# ctrlr_w_MCP4912.net
KiCad netlist of a schematic drawn in EAGLE
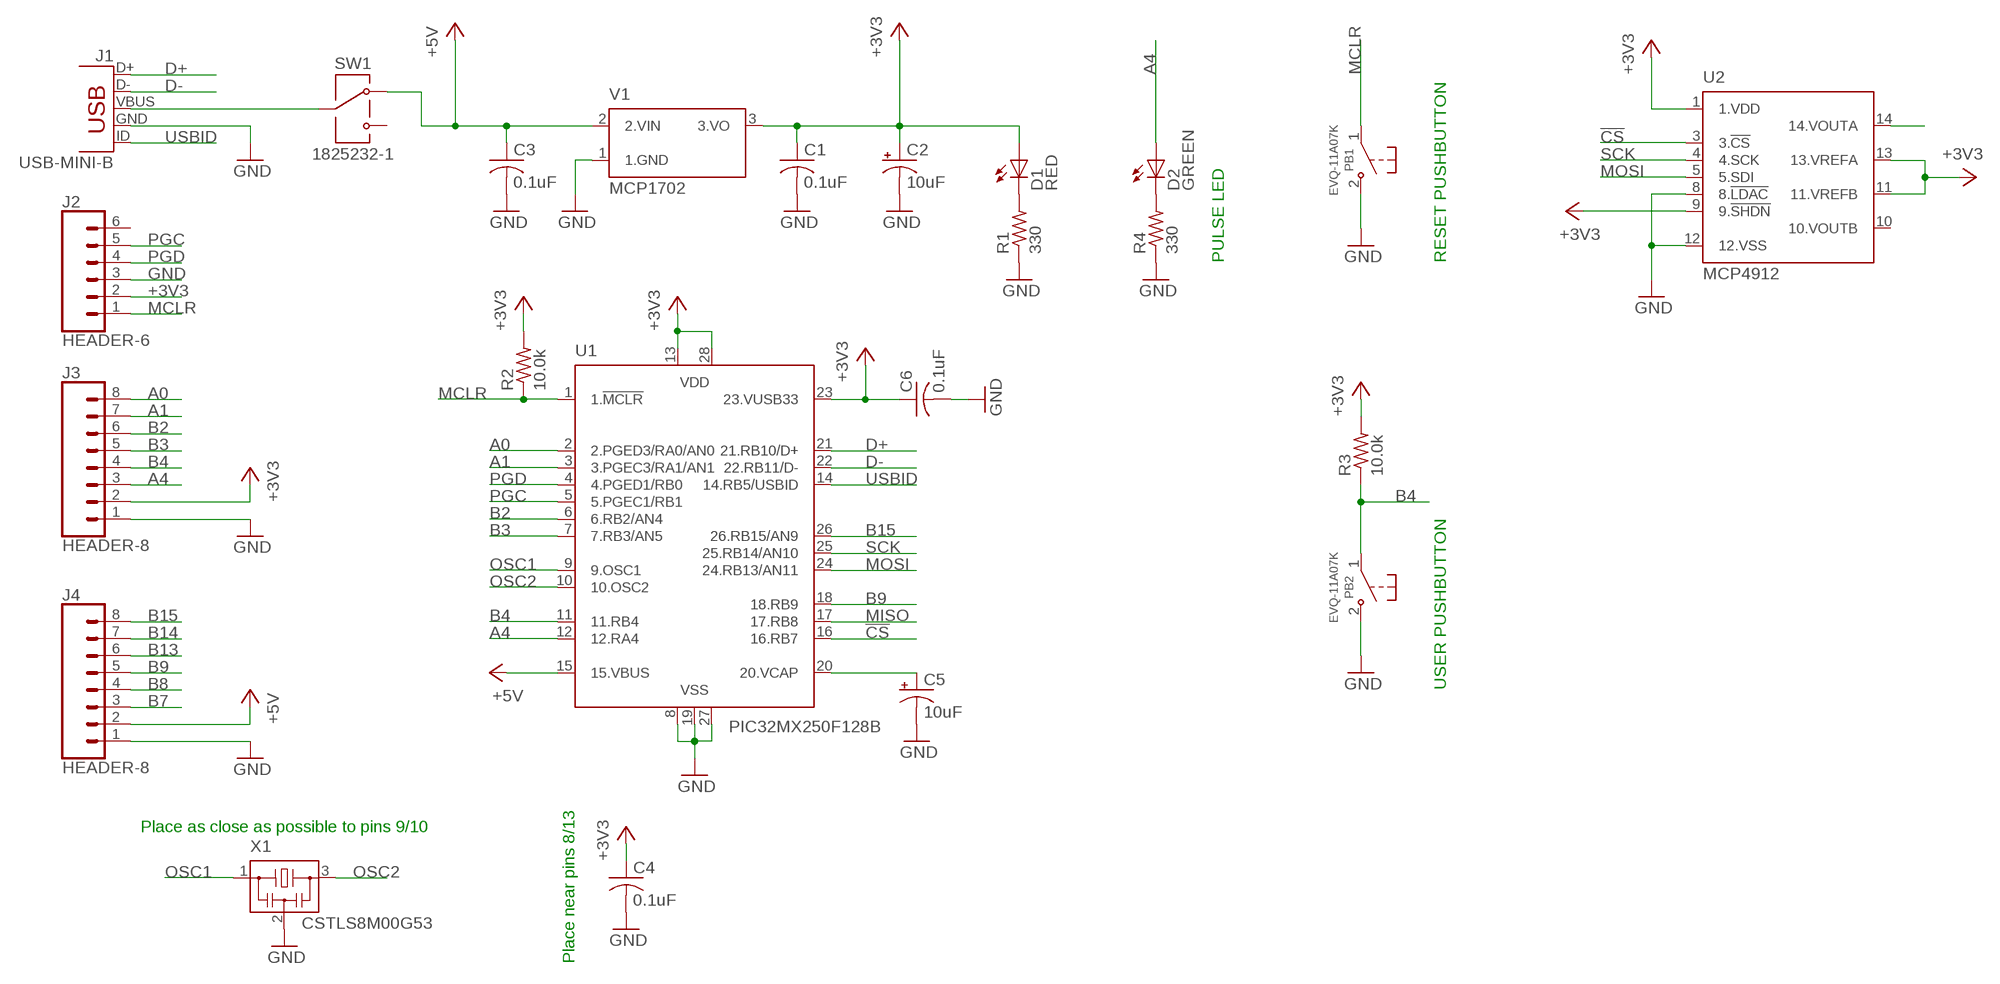
[diagram p0: schematic, sheet 1]

(export (version "E")
  (design (tool "Eeschema 10.0.6"))
  (components
    (comp (ref "C1")
      (value "0.1uF")
      (footprint "eagle-import:C1206")
      (libsource (lib "eagle-import") (part "C-USC1206"))
    )
    (comp (ref "C2")
      (value "10uF")
      (footprint "eagle-import:TAP5-50")
      (libsource (lib "eagle-import") (part "CPOL-USTAP5-50"))
    )
    (comp (ref "C3")
      (value "0.1uF")
      (footprint "eagle-import:C1206")
      (libsource (lib "eagle-import") (part "C-USC1206"))
    )
    (comp (ref "C4")
      (value "0.1uF")
      (footprint "eagle-import:C1206")
      (libsource (lib "eagle-import") (part "C-USC1206"))
    )
    (comp (ref "C5")
      (value "10uF")
      (footprint "eagle-import:TAP5-50")
      (libsource (lib "eagle-import") (part "CPOL-USTAP5-50"))
    )
    (comp (ref "C6")
      (value "0.1uF")
      (footprint "eagle-import:C1206")
      (libsource (lib "eagle-import") (part "C-USC1206"))
    )
    (comp (ref "D1")
      (value "LED-RED")
      (footprint "eagle-import:LED-3MM-V")
      (libsource (lib "eagle-import") (part "LED-RED"))
    )
    (comp (ref "D2")
      (value "LED-GREEN")
      (footprint "eagle-import:LED-3MM-V")
      (libsource (lib "eagle-import") (part "LED-GREEN"))
    )
    (comp (ref "J1")
      (value "USB-MINI-B")
      (footprint "eagle-import:USB-MB-TO")
      (libsource (lib "eagle-import") (part "USB-MINI-B"))
    )
    (comp (ref "J2")
      (value "HEADER-6")
      (footprint "eagle-import:CONN_1X06")
      (libsource (lib "eagle-import") (part "HEADER-6"))
    )
    (comp (ref "J3")
      (value "HEADER-8")
      (footprint "eagle-import:CONN_1X08")
      (libsource (lib "eagle-import") (part "HEADER-8"))
    )
    (comp (ref "J4")
      (value "HEADER-8")
      (footprint "eagle-import:CONN_1X08")
      (libsource (lib "eagle-import") (part "HEADER-8"))
    )
    (comp (ref "PB1")
      (value "EVQ-11A07K")
      (footprint "eagle-import:PCPIN-2")
      (libsource (lib "eagle-import") (part "EVQ-11A07K"))
    )
    (comp (ref "PB2")
      (value "EVQ-11A07K")
      (footprint "eagle-import:PCPIN-2")
      (libsource (lib "eagle-import") (part "EVQ-11A07K"))
    )
    (comp (ref "R1")
      (value "330")
      (footprint "eagle-import:R1206")
      (libsource (lib "eagle-import") (part "R-US_R1206"))
    )
    (comp (ref "R2")
      (value "10.0k")
      (footprint "eagle-import:R1206")
      (libsource (lib "eagle-import") (part "R-US_R1206"))
    )
    (comp (ref "R3")
      (value "10.0k")
      (footprint "eagle-import:R1206")
      (libsource (lib "eagle-import") (part "R-US_R1206"))
    )
    (comp (ref "R4")
      (value "330")
      (footprint "eagle-import:R1206")
      (libsource (lib "eagle-import") (part "R-US_R1206"))
    )
    (comp (ref "SW1")
      (value "1825232-1")
      (footprint "eagle-import:PCPIN-3SS")
      (libsource (lib "eagle-import") (part "1825232-1"))
    )
    (comp (ref "U1")
      (value "PIC32MX250F128B")
      (footprint "eagle-import:DIP28-3")
      (libsource (lib "eagle-import") (part "PIC32MX250F128B"))
    )
    (comp (ref "U2")
      (value "MCP4912")
      (footprint "eagle-import:DIP14-3")
      (libsource (lib "eagle-import") (part "MCP4912"))
    )
    (comp (ref "V1")
      (value "MCP1702")
      (footprint "eagle-import:TO-92")
      (libsource (lib "eagle-import") (part "MCP1702"))
    )
    (comp (ref "X1")
      (value "CSTLS8M00G53")
      (footprint "eagle-import:RAD-3-2.5")
      (libsource (lib "eagle-import") (part "CSTLS8M00G53"))
    )
  )
  (nets
    (net (code "1") (name "+3V3") (class "Default")
      (node (ref "C1") (pin "1") (pinfunction "1_1") (pintype "passive"))
      (node (ref "C2") (pin "+") (pinfunction "+_+") (pintype "passive"))
      (node (ref "C4") (pin "1") (pinfunction "1_1") (pintype "passive"))
      (node (ref "C6") (pin "1") (pinfunction "1_1") (pintype "passive"))
      (node (ref "D1") (pin "A") (pinfunction "A_A") (pintype "passive"))
      (node (ref "J2") (pin "2") (pinfunction "2._2") (pintype "passive"))
      (node (ref "J3") (pin "2") (pinfunction "2._2") (pintype "passive"))
      (node (ref "R2") (pin "2") (pinfunction "2_2") (pintype "passive"))
      (node (ref "R3") (pin "2") (pinfunction "2_2") (pintype "passive"))
      (node (ref "U1") (pin "13") (pinfunction "13.VDD_13") (pintype "power_in"))
      (node (ref "U1") (pin "23") (pinfunction "23.VUSB33_23") (pintype "bidirectional"))
      (node (ref "U1") (pin "28") (pinfunction "28.AVDD_28") (pintype "power_in"))
      (node (ref "U2") (pin "1") (pinfunction "1.VDD_1") (pintype "input"))
      (node (ref "U2") (pin "11") (pinfunction "11.VREFB_11") (pintype "input"))
      (node (ref "U2") (pin "13") (pinfunction "13.VREFA_13") (pintype "input"))
      (node (ref "U2") (pin "9") (pinfunction "9.~{SHDN}_9") (pintype "input"))
      (node (ref "V1") (pin "3") (pinfunction "3.VO_3") (pintype "output"))
    )
    (net (code "2") (name "+5V") (class "Default")
      (node (ref "C3") (pin "1") (pinfunction "1_1") (pintype "passive"))
      (node (ref "J4") (pin "2") (pinfunction "2._2") (pintype "passive"))
      (node (ref "SW1") (pin "1") (pinfunction "1_1") (pintype "bidirectional"))
      (node (ref "U1") (pin "15") (pinfunction "15.VBUS_15") (pintype "bidirectional"))
      (node (ref "V1") (pin "2") (pinfunction "2.VIN_2") (pintype "input"))
    )
    (net (code "3") (name "/A0") (class "Default")
      (node (ref "J3") (pin "8") (pinfunction "8._8") (pintype "passive"))
      (node (ref "U1") (pin "2") (pinfunction "2.PGED3/RA0/AN0_2") (pintype "bidirectional"))
    )
    (net (code "4") (name "/A1") (class "Default")
      (node (ref "J3") (pin "7") (pinfunction "7._7") (pintype "passive"))
      (node (ref "U1") (pin "3") (pinfunction "3.PGEC3/RA1/AN1_3") (pintype "bidirectional"))
    )
    (net (code "5") (name "/A4") (class "Default")
      (node (ref "D2") (pin "A") (pinfunction "A_A") (pintype "passive"))
      (node (ref "J3") (pin "3") (pinfunction "3._3") (pintype "passive"))
      (node (ref "U1") (pin "12") (pinfunction "12.RA4_12") (pintype "bidirectional"))
    )
    (net (code "6") (name "/B2") (class "Default")
      (node (ref "J3") (pin "6") (pinfunction "6._6") (pintype "passive"))
      (node (ref "U1") (pin "6") (pinfunction "6.RB2/AN4_6") (pintype "bidirectional"))
    )
    (net (code "7") (name "/B3") (class "Default")
      (node (ref "J3") (pin "5") (pinfunction "5._5") (pintype "passive"))
      (node (ref "U1") (pin "7") (pinfunction "7.RB3/AN5_7") (pintype "bidirectional"))
    )
    (net (code "8") (name "/B4") (class "Default")
      (node (ref "J3") (pin "4") (pinfunction "4._4") (pintype "passive"))
      (node (ref "PB2") (pin "1") (pinfunction "1.A_1") (pintype "bidirectional"))
      (node (ref "R3") (pin "1") (pinfunction "1_1") (pintype "passive"))
      (node (ref "U1") (pin "11") (pinfunction "11.RB4_11") (pintype "bidirectional"))
    )
    (net (code "9") (name "/B7") (class "Default")
      (node (ref "J4") (pin "3") (pinfunction "3._3") (pintype "passive"))
    )
    (net (code "10") (name "/B8") (class "Default")
      (node (ref "J4") (pin "4") (pinfunction "4._4") (pintype "passive"))
    )
    (net (code "11") (name "/B9") (class "Default")
      (node (ref "J4") (pin "5") (pinfunction "5._5") (pintype "passive"))
      (node (ref "U1") (pin "18") (pinfunction "18.RB9_18") (pintype "bidirectional"))
    )
    (net (code "12") (name "/B13") (class "Default")
      (node (ref "J4") (pin "6") (pinfunction "6._6") (pintype "passive"))
    )
    (net (code "13") (name "/B14") (class "Default")
      (node (ref "J4") (pin "7") (pinfunction "7._7") (pintype "passive"))
    )
    (net (code "14") (name "/B15") (class "Default")
      (node (ref "J4") (pin "8") (pinfunction "8._8") (pintype "passive"))
      (node (ref "U1") (pin "26") (pinfunction "26.RB15/AN9_26") (pintype "bidirectional"))
    )
    (net (code "15") (name "/D+") (class "Default")
      (node (ref "J1") (pin "D+") (pinfunction "D+_D+") (pintype "bidirectional"))
      (node (ref "U1") (pin "21") (pinfunction "21.RB10/D+_21") (pintype "bidirectional"))
    )
    (net (code "16") (name "/D-") (class "Default")
      (node (ref "J1") (pin "D-") (pinfunction "D-_D-") (pintype "bidirectional"))
      (node (ref "U1") (pin "22") (pinfunction "22.RB11/D-_22") (pintype "bidirectional"))
    )
    (net (code "17") (name "/MCLR") (class "Default")
      (node (ref "J2") (pin "1") (pinfunction "1._1") (pintype "passive"))
      (node (ref "PB1") (pin "1") (pinfunction "1.A_1") (pintype "bidirectional"))
      (node (ref "R2") (pin "1") (pinfunction "1_1") (pintype "passive"))
      (node (ref "U1") (pin "1") (pinfunction "1.~{MCLR}_1") (pintype "input"))
    )
    (net (code "18") (name "/MISO") (class "Default")
      (node (ref "U1") (pin "17") (pinfunction "17.RB8_17") (pintype "bidirectional"))
    )
    (net (code "19") (name "/MOSI") (class "Default")
      (node (ref "U1") (pin "24") (pinfunction "24.RB13/AN11_24") (pintype "bidirectional"))
      (node (ref "U2") (pin "5") (pinfunction "5.SDI_5") (pintype "input"))
    )
    (net (code "20") (name "/OSC1") (class "Default")
      (node (ref "U1") (pin "9") (pinfunction "9.OSC1_9") (pintype "input"))
      (node (ref "X1") (pin "1") (pinfunction "1_1") (pintype "passive"))
    )
    (net (code "21") (name "/OSC2") (class "Default")
      (node (ref "U1") (pin "10") (pinfunction "10.OSC2_10") (pintype "output"))
      (node (ref "X1") (pin "3") (pinfunction "3_3") (pintype "passive"))
    )
    (net (code "22") (name "/PGC") (class "Default")
      (node (ref "J2") (pin "5") (pinfunction "5._5") (pintype "passive"))
      (node (ref "U1") (pin "5") (pinfunction "5.PGEC1/RB1_5") (pintype "bidirectional"))
    )
    (net (code "23") (name "/PGD") (class "Default")
      (node (ref "J2") (pin "4") (pinfunction "4._4") (pintype "passive"))
      (node (ref "U1") (pin "4") (pinfunction "4.PGED1/RB0_4") (pintype "bidirectional"))
    )
    (net (code "24") (name "/SCK") (class "Default")
      (node (ref "U1") (pin "25") (pinfunction "25.RB14/AN10_25") (pintype "bidirectional"))
      (node (ref "U2") (pin "4") (pinfunction "4.SCK_4") (pintype "input"))
    )
    (net (code "25") (name "/USBID") (class "Default")
      (node (ref "J1") (pin "ID") (pinfunction "ID_ID") (pintype "bidirectional"))
      (node (ref "U1") (pin "14") (pinfunction "14.RB5/USBID_14") (pintype "bidirectional"))
    )
    (net (code "26") (name "/~{CS}") (class "Default")
      (node (ref "U1") (pin "16") (pinfunction "16.RB7_16") (pintype "bidirectional"))
      (node (ref "U2") (pin "3") (pinfunction "3.~{CS}_3") (pintype "input"))
    )
    (net (code "27") (name "GND") (class "Default")
      (node (ref "C1") (pin "2") (pinfunction "2_2") (pintype "passive"))
      (node (ref "C2") (pin "-") (pinfunction "-_-") (pintype "passive"))
      (node (ref "C3") (pin "2") (pinfunction "2_2") (pintype "passive"))
      (node (ref "C4") (pin "2") (pinfunction "2_2") (pintype "passive"))
      (node (ref "C5") (pin "-") (pinfunction "-_-") (pintype "passive"))
      (node (ref "C6") (pin "2") (pinfunction "2_2") (pintype "passive"))
      (node (ref "J1") (pin "GND") (pinfunction "GND_GND") (pintype "bidirectional"))
      (node (ref "J2") (pin "3") (pinfunction "3._3") (pintype "passive"))
      (node (ref "J3") (pin "1") (pinfunction "1._1") (pintype "passive"))
      (node (ref "J4") (pin "1") (pinfunction "1._1") (pintype "passive"))
      (node (ref "PB1") (pin "2") (pinfunction "2.B_2") (pintype "bidirectional"))
      (node (ref "PB2") (pin "2") (pinfunction "2.B_2") (pintype "bidirectional"))
      (node (ref "R1") (pin "1") (pinfunction "1_1") (pintype "passive"))
      (node (ref "R4") (pin "1") (pinfunction "1_1") (pintype "passive"))
      (node (ref "U1") (pin "19") (pinfunction "19.VSS_19") (pintype "power_in"))
      (node (ref "U1") (pin "27") (pinfunction "27.AVSS_27") (pintype "bidirectional"))
      (node (ref "U1") (pin "8") (pinfunction "8.VSS_8") (pintype "power_in"))
      (node (ref "U2") (pin "12") (pinfunction "12.VSS_12") (pintype "input"))
      (node (ref "U2") (pin "8") (pinfunction "8.~{LDAC}_8") (pintype "input"))
      (node (ref "V1") (pin "1") (pinfunction "1.GND_1") (pintype "passive"))
      (node (ref "X1") (pin "2") (pinfunction "2_2") (pintype "passive"))
    )
    (net (code "28") (name "Net-(D1-C)") (class "Default")
      (node (ref "D1") (pin "K") (pinfunction "C_K") (pintype "passive"))
      (node (ref "R1") (pin "2") (pinfunction "2_2") (pintype "passive"))
    )
    (net (code "29") (name "Net-(D2-C)") (class "Default")
      (node (ref "D2") (pin "K") (pinfunction "C_K") (pintype "passive"))
      (node (ref "R4") (pin "2") (pinfunction "2_2") (pintype "passive"))
    )
    (net (code "30") (name "Net-(J1-PadVBUS)") (class "Default")
      (node (ref "J1") (pin "VBUS") (pinfunction "VBUS_VBUS") (pintype "bidirectional"))
      (node (ref "SW1") (pin "2") (pinfunction "2_2") (pintype "bidirectional"))
    )
    (net (code "31") (name "Net-(U1-20.VCAP)") (class "Default")
      (node (ref "C5") (pin "+") (pinfunction "+_+") (pintype "passive"))
      (node (ref "U1") (pin "20") (pinfunction "20.VCAP_20") (pintype "bidirectional"))
    )
    (net (code "32") (name "unconnected-(J2-6.-Pad6)") (class "Default")
      (node (ref "J2") (pin "6") (pinfunction "6._6") (pintype "passive"))
    )
    (net (code "33") (name "unconnected-(SW1-Pad3)") (class "Default")
      (node (ref "SW1") (pin "3") (pinfunction "3_3") (pintype "bidirectional"))
    )
    (net (code "34") (name "unconnected-(U2-10.VOUTB-Pad10)") (class "Default")
      (node (ref "U2") (pin "10") (pinfunction "10.VOUTB_10") (pintype "input"))
    )
    (net (code "35") (name "unconnected-(U2-14.VOUTA-Pad14)") (class "Default")
      (node (ref "U2") (pin "14") (pinfunction "14.VOUTA_14") (pintype "input"))
    )
  )
)
